# Connector-Side-2.net
KiCad netlist of a schematic drawn in Altium Designer
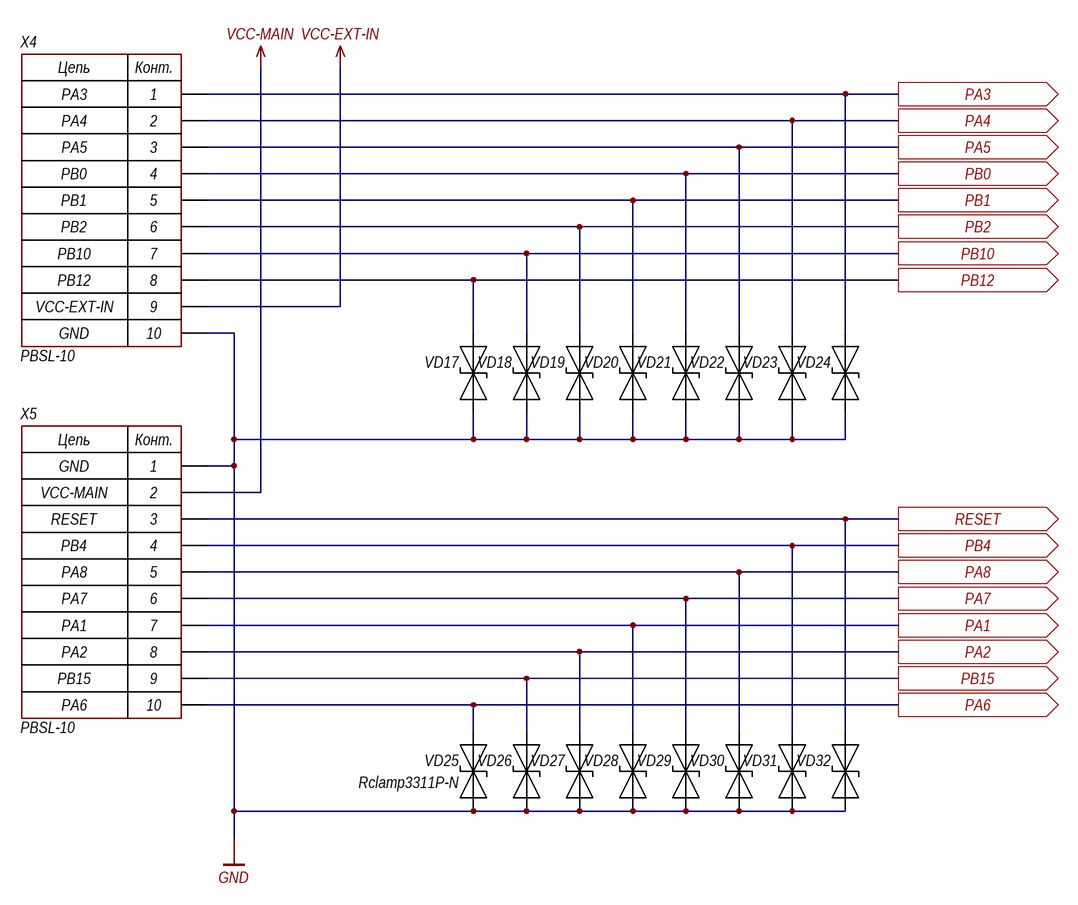
[diagram p0: Connector-Side-2.SchDoc]

(export (version "E")
  (design (tool "Eeschema 10.0.6"))
  (components
    (comp (ref "VD17")
      (value "Rclamp3311P-N")
      (footprint "DFN1006-2")
      (fields (field (name "MANUFACTURER") "BORN"))
      (libsource (lib "Diods") (part "TVS-diod"))
    )
    (comp (ref "VD18")
      (value "Rclamp3311P-N")
      (footprint "DFN1006-2")
      (fields (field (name "MANUFACTURER") "BORN"))
      (libsource (lib "Diods") (part "TVS-diod"))
    )
    (comp (ref "VD19")
      (value "Rclamp3311P-N")
      (footprint "DFN1006-2")
      (fields (field (name "MANUFACTURER") "BORN"))
      (libsource (lib "Diods") (part "TVS-diod"))
    )
    (comp (ref "VD20")
      (value "Rclamp3311P-N")
      (footprint "DFN1006-2")
      (fields (field (name "MANUFACTURER") "BORN"))
      (libsource (lib "Diods") (part "TVS-diod"))
    )
    (comp (ref "VD21")
      (value "Rclamp3311P-N")
      (footprint "DFN1006-2")
      (fields (field (name "MANUFACTURER") "BORN"))
      (libsource (lib "Diods") (part "TVS-diod"))
    )
    (comp (ref "VD22")
      (value "Rclamp3311P-N")
      (footprint "DFN1006-2")
      (fields (field (name "MANUFACTURER") "BORN"))
      (libsource (lib "Diods") (part "TVS-diod"))
    )
    (comp (ref "VD23")
      (value "Rclamp3311P-N")
      (footprint "DFN1006-2")
      (fields (field (name "MANUFACTURER") "BORN"))
      (libsource (lib "Diods") (part "TVS-diod"))
    )
    (comp (ref "VD24")
      (value "Rclamp3311P-N")
      (footprint "DFN1006-2")
      (fields (field (name "MANUFACTURER") "BORN"))
      (libsource (lib "Diods") (part "TVS-diod"))
    )
    (comp (ref "VD25")
      (value "Rclamp3311P-N")
      (footprint "DFN1006-2")
      (fields (field (name "MANUFACTURER") "BORN"))
      (libsource (lib "Diods") (part "TVS-diod"))
    )
    (comp (ref "VD26")
      (value "Rclamp3311P-N")
      (footprint "DFN1006-2")
      (fields (field (name "MANUFACTURER") "BORN"))
      (libsource (lib "Diods") (part "TVS-diod"))
    )
    (comp (ref "VD27")
      (value "Rclamp3311P-N")
      (footprint "DFN1006-2")
      (fields (field (name "MANUFACTURER") "BORN"))
      (libsource (lib "Diods") (part "TVS-diod"))
    )
    (comp (ref "VD28")
      (value "Rclamp3311P-N")
      (footprint "DFN1006-2")
      (fields (field (name "MANUFACTURER") "BORN"))
      (libsource (lib "Diods") (part "TVS-diod"))
    )
    (comp (ref "VD29")
      (value "Rclamp3311P-N")
      (footprint "DFN1006-2")
      (fields (field (name "MANUFACTURER") "BORN"))
      (libsource (lib "Diods") (part "TVS-diod"))
    )
    (comp (ref "VD30")
      (value "Rclamp3311P-N")
      (footprint "DFN1006-2")
      (fields (field (name "MANUFACTURER") "BORN"))
      (libsource (lib "Diods") (part "TVS-diod"))
    )
    (comp (ref "VD31")
      (value "Rclamp3311P-N")
      (footprint "DFN1006-2")
      (fields (field (name "MANUFACTURER") "BORN"))
      (libsource (lib "Diods") (part "TVS-diod"))
    )
    (comp (ref "VD32")
      (value "Rclamp3311P-N")
      (footprint "DFN1006-2")
      (fields (field (name "MANUFACTURER") "BORN"))
      (libsource (lib "Diods") (part "TVS-diod"))
    )
    (comp (ref "X4")
      (value "PBSL-10")
      (footprint "CON: PBSL-10")
      (libsource (lib "Connectors") (part "10-Connector"))
    )
    (comp (ref "X5")
      (value "PBSL-10")
      (footprint "CON: PBSL-10")
      (libsource (lib "Connectors") (part "10-Connector"))
    )
  )
  (nets
    (net (code "1") (name "/PA1") (class "Default")
      (node (ref "VD28") (pin "2") (pinfunction "C_2") (pintype "passive"))
      (node (ref "X5") (pin "7") (pinfunction "7_7") (pintype "passive"))
    )
    (net (code "2") (name "/PA2") (class "Default")
      (node (ref "VD27") (pin "2") (pinfunction "C_2") (pintype "passive"))
      (node (ref "X5") (pin "8") (pinfunction "8_8") (pintype "passive"))
    )
    (net (code "3") (name "/PA3") (class "Default")
      (node (ref "VD24") (pin "2") (pinfunction "C_2") (pintype "passive"))
      (node (ref "X4") (pin "1") (pinfunction "1_1") (pintype "passive"))
    )
    (net (code "4") (name "/PA4") (class "Default")
      (node (ref "VD23") (pin "2") (pinfunction "C_2") (pintype "passive"))
      (node (ref "X4") (pin "2") (pinfunction "2_2") (pintype "passive"))
    )
    (net (code "5") (name "/PA5") (class "Default")
      (node (ref "VD22") (pin "2") (pinfunction "C_2") (pintype "passive"))
      (node (ref "X4") (pin "3") (pinfunction "3_3") (pintype "passive"))
    )
    (net (code "6") (name "/PA6") (class "Default")
      (node (ref "VD25") (pin "2") (pinfunction "C_2") (pintype "passive"))
      (node (ref "X5") (pin "10") (pinfunction "10_10") (pintype "passive"))
    )
    (net (code "7") (name "/PA7") (class "Default")
      (node (ref "VD29") (pin "2") (pinfunction "C_2") (pintype "passive"))
      (node (ref "X5") (pin "6") (pinfunction "6_6") (pintype "passive"))
    )
    (net (code "8") (name "/PA8") (class "Default")
      (node (ref "VD30") (pin "2") (pinfunction "C_2") (pintype "passive"))
      (node (ref "X5") (pin "5") (pinfunction "5_5") (pintype "passive"))
    )
    (net (code "9") (name "/PB0") (class "Default")
      (node (ref "VD21") (pin "2") (pinfunction "C_2") (pintype "passive"))
      (node (ref "X4") (pin "4") (pinfunction "4_4") (pintype "passive"))
    )
    (net (code "10") (name "/PB1") (class "Default")
      (node (ref "VD20") (pin "2") (pinfunction "C_2") (pintype "passive"))
      (node (ref "X4") (pin "5") (pinfunction "5_5") (pintype "passive"))
    )
    (net (code "11") (name "/PB2") (class "Default")
      (node (ref "VD19") (pin "2") (pinfunction "C_2") (pintype "passive"))
      (node (ref "X4") (pin "6") (pinfunction "6_6") (pintype "passive"))
    )
    (net (code "12") (name "/PB4") (class "Default")
      (node (ref "VD31") (pin "2") (pinfunction "C_2") (pintype "passive"))
      (node (ref "X5") (pin "4") (pinfunction "4_4") (pintype "passive"))
    )
    (net (code "13") (name "/PB10") (class "Default")
      (node (ref "VD18") (pin "2") (pinfunction "C_2") (pintype "passive"))
      (node (ref "X4") (pin "7") (pinfunction "7_7") (pintype "passive"))
    )
    (net (code "14") (name "/PB12") (class "Default")
      (node (ref "VD17") (pin "2") (pinfunction "C_2") (pintype "passive"))
      (node (ref "X4") (pin "8") (pinfunction "8_8") (pintype "passive"))
    )
    (net (code "15") (name "/PB15") (class "Default")
      (node (ref "VD26") (pin "2") (pinfunction "C_2") (pintype "passive"))
      (node (ref "X5") (pin "9") (pinfunction "9_9") (pintype "passive"))
    )
    (net (code "16") (name "/RESET") (class "Default")
      (node (ref "VD32") (pin "2") (pinfunction "C_2") (pintype "passive"))
      (node (ref "X5") (pin "3") (pinfunction "3_3") (pintype "passive"))
    )
    (net (code "17") (name "GND") (class "Default")
      (node (ref "VD17") (pin "1") (pinfunction "A_1") (pintype "passive"))
      (node (ref "VD18") (pin "1") (pinfunction "A_1") (pintype "passive"))
      (node (ref "VD19") (pin "1") (pinfunction "A_1") (pintype "passive"))
      (node (ref "VD20") (pin "1") (pinfunction "A_1") (pintype "passive"))
      (node (ref "VD21") (pin "1") (pinfunction "A_1") (pintype "passive"))
      (node (ref "VD22") (pin "1") (pinfunction "A_1") (pintype "passive"))
      (node (ref "VD23") (pin "1") (pinfunction "A_1") (pintype "passive"))
      (node (ref "VD24") (pin "1") (pinfunction "A_1") (pintype "passive"))
      (node (ref "VD25") (pin "1") (pinfunction "A_1") (pintype "passive"))
      (node (ref "VD26") (pin "1") (pinfunction "A_1") (pintype "passive"))
      (node (ref "VD27") (pin "1") (pinfunction "A_1") (pintype "passive"))
      (node (ref "VD28") (pin "1") (pinfunction "A_1") (pintype "passive"))
      (node (ref "VD29") (pin "1") (pinfunction "A_1") (pintype "passive"))
      (node (ref "VD30") (pin "1") (pinfunction "A_1") (pintype "passive"))
      (node (ref "VD31") (pin "1") (pinfunction "A_1") (pintype "passive"))
      (node (ref "VD32") (pin "1") (pinfunction "A_1") (pintype "passive"))
      (node (ref "X4") (pin "10") (pinfunction "10_10") (pintype "passive"))
      (node (ref "X5") (pin "1") (pinfunction "1_1") (pintype "passive"))
    )
    (net (code "18") (name "VCC-EXT-IN") (class "Default")
      (node (ref "X4") (pin "9") (pinfunction "9_9") (pintype "passive"))
    )
    (net (code "19") (name "VCC-MAIN") (class "Default")
      (node (ref "X5") (pin "2") (pinfunction "2_2") (pintype "passive"))
    )
  )
)
